# BEMF_Sense.net
KiCad netlist of a schematic drawn in Altium Designer
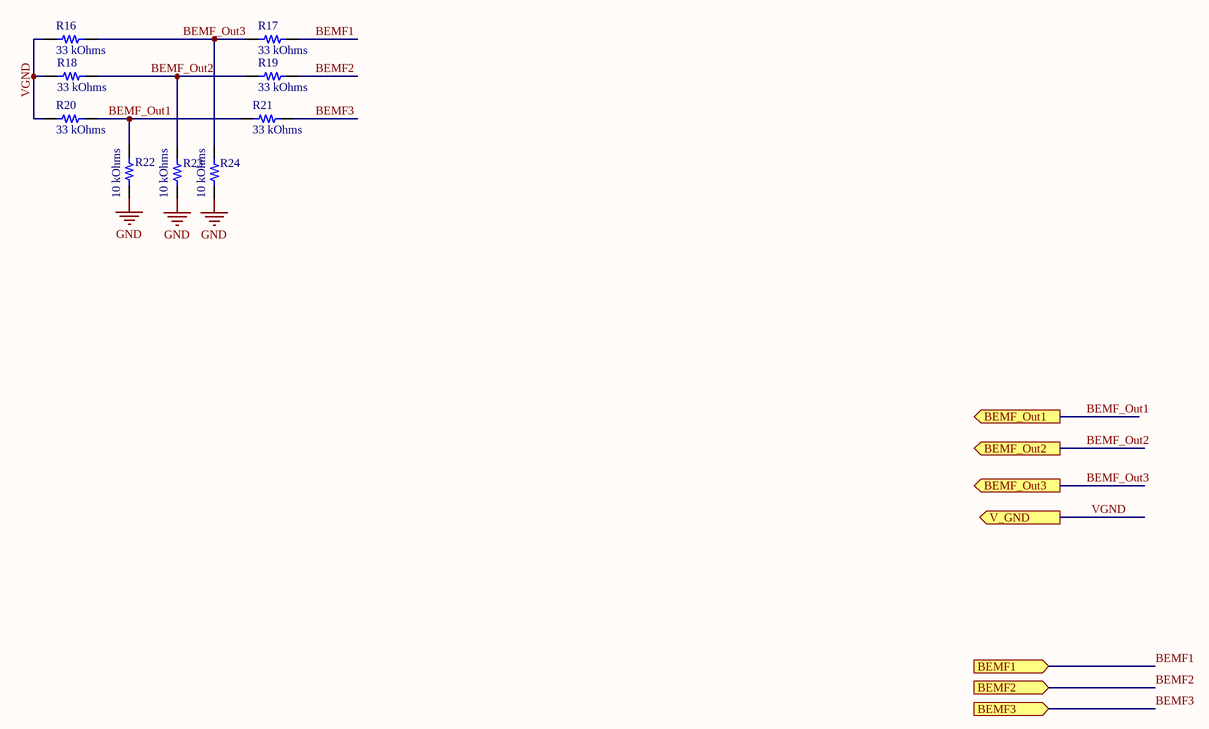
[diagram p0: BEMF_Sense.SchDoc]

(export (version "E")
  (design (tool "Eeschema 10.0.6"))
  (components
    (comp (ref "R16")
      (value "33 kOhms")
      (footprint "RES 0805_2012")
      (description "RES SMD 33K OHM 1% 1/8W 0805")
      (fields (field (name "PART NUMBER") "CR0805-FX-3302ELF") (field (name "MANUFACTURER") "Bourns Inc."))
      (libsource (lib "Celestial Altium Library - altium_library") (part "Resistor"))
    )
    (comp (ref "R17")
      (value "33 kOhms")
      (footprint "RES 0805_2012")
      (description "RES SMD 33K OHM 1% 1/8W 0805")
      (fields (field (name "PART NUMBER") "CR0805-FX-3302ELF") (field (name "MANUFACTURER") "Bourns Inc."))
      (libsource (lib "Celestial Altium Library - altium_library") (part "Resistor"))
    )
    (comp (ref "R18")
      (value "33 kOhms")
      (footprint "RES 0805_2012")
      (description "RES SMD 33K OHM 1% 1/8W 0805")
      (fields (field (name "PART NUMBER") "CR0805-FX-3302ELF") (field (name "MANUFACTURER") "Bourns Inc."))
      (libsource (lib "Celestial Altium Library - altium_library") (part "Resistor"))
    )
    (comp (ref "R19")
      (value "33 kOhms")
      (footprint "RES 0805_2012")
      (description "RES SMD 33K OHM 1% 1/8W 0805")
      (fields (field (name "PART NUMBER") "CR0805-FX-3302ELF") (field (name "MANUFACTURER") "Bourns Inc."))
      (libsource (lib "Celestial Altium Library - altium_library") (part "Resistor"))
    )
    (comp (ref "R20")
      (value "33 kOhms")
      (footprint "RES 0805_2012")
      (description "RES SMD 33K OHM 1% 1/8W 0805")
      (fields (field (name "PART NUMBER") "CR0805-FX-3302ELF") (field (name "MANUFACTURER") "Bourns Inc."))
      (libsource (lib "Celestial Altium Library - altium_library") (part "Resistor"))
    )
    (comp (ref "R21")
      (value "33 kOhms")
      (footprint "RES 0805_2012")
      (description "RES SMD 33K OHM 1% 1/8W 0805")
      (fields (field (name "PART NUMBER") "CR0805-FX-3302ELF") (field (name "MANUFACTURER") "Bourns Inc."))
      (libsource (lib "Celestial Altium Library - altium_library") (part "Resistor"))
    )
    (comp (ref "R22")
      (value "10 kOhms")
      (footprint "RES 0805_2012")
      (description "RES 10K OHM 1% 1/8W 0805")
      (fields
        (field (name "PART NUMBER") "RN73R2ATTD1002F25")
        (field (name "MANUFACTURER") "KOA Speer Electronics, Inc.")
      )
      (libsource (lib "Celestial Altium Library - altium_library") (part "Resistor"))
    )
    (comp (ref "R23")
      (value "10 kOhms")
      (footprint "RES 0805_2012")
      (description "RES 10K OHM 1% 1/8W 0805")
      (fields
        (field (name "PART NUMBER") "RN73R2ATTD1002F25")
        (field (name "MANUFACTURER") "KOA Speer Electronics, Inc.")
      )
      (libsource (lib "Celestial Altium Library - altium_library") (part "Resistor"))
    )
    (comp (ref "R24")
      (value "10 kOhms")
      (footprint "RES 0805_2012")
      (description "RES 10K OHM 1% 1/8W 0805")
      (fields
        (field (name "PART NUMBER") "RN73R2ATTD1002F25")
        (field (name "MANUFACTURER") "KOA Speer Electronics, Inc.")
      )
      (libsource (lib "Celestial Altium Library - altium_library") (part "Resistor"))
    )
  )
  (nets
    (net (code "1") (name "/BEMF1") (class "Default")
      (node (ref "R17") (pin "2") (pinfunction "2_2") (pintype "passive"))
    )
    (net (code "2") (name "/BEMF2") (class "Default")
      (node (ref "R19") (pin "2") (pinfunction "2_2") (pintype "passive"))
    )
    (net (code "3") (name "/BEMF3") (class "Default")
      (node (ref "R21") (pin "2") (pinfunction "2_2") (pintype "passive"))
    )
    (net (code "4") (name "/BEMF_Out1") (class "Default")
      (node (ref "R20") (pin "2") (pinfunction "2_2") (pintype "passive"))
      (node (ref "R21") (pin "1") (pinfunction "1_1") (pintype "passive"))
      (node (ref "R22") (pin "2") (pinfunction "2_2") (pintype "passive"))
    )
    (net (code "5") (name "/BEMF_Out2") (class "Default")
      (node (ref "R18") (pin "2") (pinfunction "2_2") (pintype "passive"))
      (node (ref "R19") (pin "1") (pinfunction "1_1") (pintype "passive"))
      (node (ref "R23") (pin "2") (pinfunction "2_2") (pintype "passive"))
    )
    (net (code "6") (name "/BEMF_Out3") (class "Default")
      (node (ref "R16") (pin "2") (pinfunction "2_2") (pintype "passive"))
      (node (ref "R17") (pin "1") (pinfunction "1_1") (pintype "passive"))
      (node (ref "R24") (pin "2") (pinfunction "2_2") (pintype "passive"))
    )
    (net (code "7") (name "/VGND") (class "Default")
      (node (ref "R16") (pin "1") (pinfunction "1_1") (pintype "passive"))
      (node (ref "R18") (pin "1") (pinfunction "1_1") (pintype "passive"))
      (node (ref "R20") (pin "1") (pinfunction "1_1") (pintype "passive"))
    )
    (net (code "8") (name "GND") (class "Default")
      (node (ref "R22") (pin "1") (pinfunction "1_1") (pintype "passive"))
      (node (ref "R23") (pin "1") (pinfunction "1_1") (pintype "passive"))
      (node (ref "R24") (pin "1") (pinfunction "1_1") (pintype "passive"))
    )
  )
)
